# Ararinha4.net
KiCad netlist of a schematic drawn in EAGLE
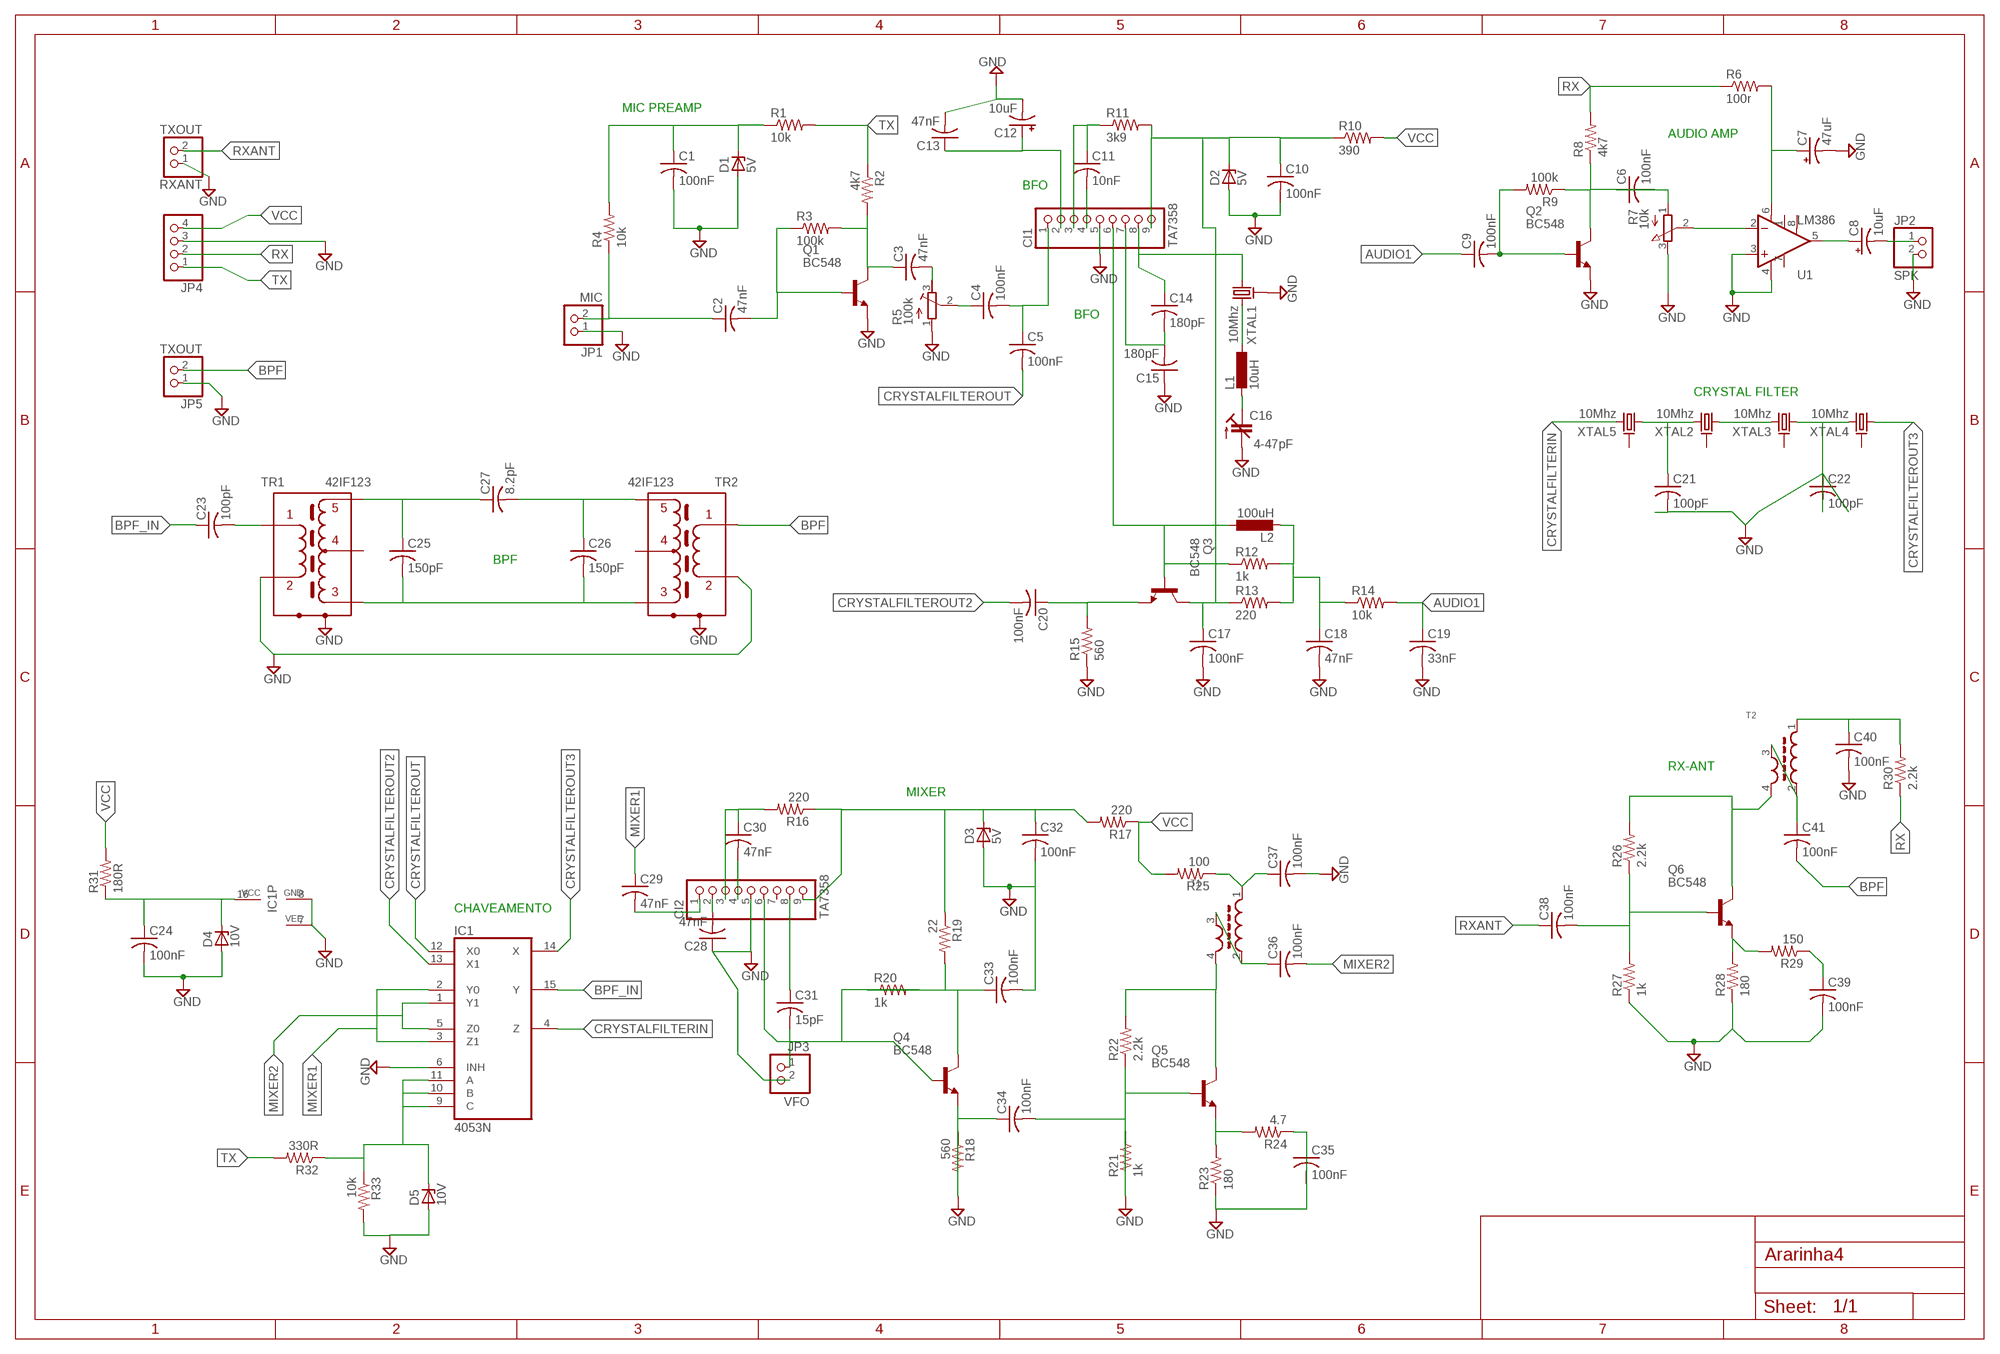
[diagram p0: schematic, sheet 1]

(export (version "E")
  (design (tool "Eeschema 10.0.6"))
  (components
    (comp (ref "C1")
      (value "100nF")
      (footprint "eagle-import:C050-030X075")
      (libsource (lib "eagle-import") (part "C-US050-030X075"))
    )
    (comp (ref "C2")
      (value "47nF")
      (footprint "eagle-import:C050-030X075")
      (libsource (lib "eagle-import") (part "C-US050-030X075"))
    )
    (comp (ref "C3")
      (value "47nF")
      (footprint "eagle-import:C050-030X075")
      (libsource (lib "eagle-import") (part "C-US050-030X075"))
    )
    (comp (ref "C4")
      (value "100nF")
      (footprint "eagle-import:C050-030X075")
      (libsource (lib "eagle-import") (part "C-US050-030X075"))
    )
    (comp (ref "C5")
      (value "100nF")
      (footprint "eagle-import:C050-030X075")
      (libsource (lib "eagle-import") (part "C-US050-030X075"))
    )
    (comp (ref "C6")
      (value "100nF")
      (footprint "eagle-import:C050-030X075")
      (libsource (lib "eagle-import") (part "C-US050-030X075"))
    )
    (comp (ref "C7")
      (value "47uF")
      (footprint "eagle-import:E5-6")
      (libsource (lib "eagle-import") (part "CPOL-USE5-6"))
    )
    (comp (ref "C8")
      (value "10uF")
      (footprint "eagle-import:E5-6")
      (libsource (lib "eagle-import") (part "CPOL-USE5-6"))
    )
    (comp (ref "C9")
      (value "100nF")
      (footprint "eagle-import:C050-030X075")
      (libsource (lib "eagle-import") (part "C-US050-030X075"))
    )
    (comp (ref "C10")
      (value "100nF")
      (footprint "eagle-import:C050-030X075")
      (libsource (lib "eagle-import") (part "C-US050-030X075"))
    )
    (comp (ref "C11")
      (value "10nF")
      (footprint "eagle-import:C050-030X075")
      (libsource (lib "eagle-import") (part "C-US050-030X075"))
    )
    (comp (ref "C12")
      (value "10uF")
      (footprint "eagle-import:E5-6")
      (libsource (lib "eagle-import") (part "CPOL-USE5-6"))
    )
    (comp (ref "C13")
      (value "47nF")
      (footprint "eagle-import:C050-030X075")
      (libsource (lib "eagle-import") (part "C-US050-030X075"))
    )
    (comp (ref "C14")
      (value "180pF")
      (footprint "eagle-import:C050-030X075")
      (libsource (lib "eagle-import") (part "C-US050-030X075"))
    )
    (comp (ref "C15")
      (value "180pF")
      (footprint "eagle-import:C050-030X075")
      (libsource (lib "eagle-import") (part "C-US050-030X075"))
    )
    (comp (ref "C16")
      (value "4-47pF")
      (footprint "eagle-import:CTRIM3050.504")
      (libsource (lib "eagle-import") (part "C-TRIMM3050.504"))
    )
    (comp (ref "C17")
      (value "100nF")
      (footprint "eagle-import:C050-030X075")
      (libsource (lib "eagle-import") (part "C-US050-030X075"))
    )
    (comp (ref "C18")
      (value "47nF")
      (footprint "eagle-import:C050-030X075")
      (libsource (lib "eagle-import") (part "C-US050-030X075"))
    )
    (comp (ref "C19")
      (value "33nF")
      (footprint "eagle-import:C050-030X075")
      (libsource (lib "eagle-import") (part "C-US050-030X075"))
    )
    (comp (ref "C20")
      (value "100nF")
      (footprint "eagle-import:C050-030X075")
      (libsource (lib "eagle-import") (part "C-US050-030X075"))
    )
    (comp (ref "C21")
      (value "100pF")
      (footprint "eagle-import:C050-030X075")
      (libsource (lib "eagle-import") (part "C-US050-030X075"))
    )
    (comp (ref "C22")
      (value "100pF")
      (footprint "eagle-import:C050-030X075")
      (libsource (lib "eagle-import") (part "C-US050-030X075"))
    )
    (comp (ref "C23")
      (value "100pF")
      (footprint "eagle-import:C050-030X075")
      (libsource (lib "eagle-import") (part "C-US050-030X075"))
    )
    (comp (ref "C24")
      (value "100nF")
      (footprint "eagle-import:C050-030X075")
      (libsource (lib "eagle-import") (part "C-US050-030X075"))
    )
    (comp (ref "C25")
      (value "150pF")
      (footprint "eagle-import:C050-030X075")
      (libsource (lib "eagle-import") (part "C-US050-030X075"))
    )
    (comp (ref "C26")
      (value "150pF")
      (footprint "eagle-import:C050-030X075")
      (libsource (lib "eagle-import") (part "C-US050-030X075"))
    )
    (comp (ref "C27")
      (value "8.2pF")
      (footprint "eagle-import:C050-030X075")
      (libsource (lib "eagle-import") (part "C-US050-030X075"))
    )
    (comp (ref "C28")
      (value "47nF")
      (footprint "eagle-import:C050-030X075")
      (libsource (lib "eagle-import") (part "C-US050-030X075"))
    )
    (comp (ref "C29")
      (value "47nF")
      (footprint "eagle-import:C050-030X075")
      (libsource (lib "eagle-import") (part "C-US050-030X075"))
    )
    (comp (ref "C30")
      (value "47nF")
      (footprint "eagle-import:C050-030X075")
      (libsource (lib "eagle-import") (part "C-US050-030X075"))
    )
    (comp (ref "C31")
      (value "15pF")
      (footprint "eagle-import:C050-030X075")
      (libsource (lib "eagle-import") (part "C-US050-030X075"))
    )
    (comp (ref "C32")
      (value "100nF")
      (footprint "eagle-import:C050-030X075")
      (libsource (lib "eagle-import") (part "C-US050-030X075"))
    )
    (comp (ref "C33")
      (value "100nF")
      (footprint "eagle-import:C050-030X075")
      (libsource (lib "eagle-import") (part "C-US050-030X075"))
    )
    (comp (ref "C34")
      (value "100nF")
      (footprint "eagle-import:C050-030X075")
      (libsource (lib "eagle-import") (part "C-US050-030X075"))
    )
    (comp (ref "C35")
      (value "100nF")
      (footprint "eagle-import:C050-030X075")
      (libsource (lib "eagle-import") (part "C-US050-030X075"))
    )
    (comp (ref "C36")
      (value "100nF")
      (footprint "eagle-import:C050-030X075")
      (libsource (lib "eagle-import") (part "C-US050-030X075"))
    )
    (comp (ref "C37")
      (value "100nF")
      (footprint "eagle-import:C050-030X075")
      (libsource (lib "eagle-import") (part "C-US050-030X075"))
    )
    (comp (ref "C38")
      (value "100nF")
      (footprint "eagle-import:C050-030X075")
      (libsource (lib "eagle-import") (part "C-US050-030X075"))
    )
    (comp (ref "C39")
      (value "100nF")
      (footprint "eagle-import:C050-030X075")
      (libsource (lib "eagle-import") (part "C-US050-030X075"))
    )
    (comp (ref "C40")
      (value "100nF")
      (footprint "eagle-import:C050-030X075")
      (libsource (lib "eagle-import") (part "C-US050-030X075"))
    )
    (comp (ref "C41")
      (value "100nF")
      (footprint "eagle-import:C050-030X075")
      (libsource (lib "eagle-import") (part "C-US050-030X075"))
    )
    (comp (ref "CI1")
      (value "TA7358")
      (footprint "eagle-import:1X09")
      (libsource (lib "eagle-import") (part "PINHD-1X9"))
    )
    (comp (ref "CI2")
      (value "TA7358")
      (footprint "eagle-import:1X09")
      (libsource (lib "eagle-import") (part "PINHD-1X9"))
    )
    (comp (ref "D1")
      (value "5V")
      (footprint "eagle-import:ZDIO-5")
      (libsource (lib "eagle-import") (part "ZENER-DIODEZD-5"))
    )
    (comp (ref "D2")
      (value "5V")
      (footprint "eagle-import:ZDIO-5")
      (libsource (lib "eagle-import") (part "ZENER-DIODEZD-5"))
    )
    (comp (ref "D3")
      (value "5V")
      (footprint "eagle-import:ZDIO-5")
      (libsource (lib "eagle-import") (part "ZENER-DIODEZD-5"))
    )
    (comp (ref "D4")
      (value "10V")
      (footprint "eagle-import:ZDIO-5")
      (libsource (lib "eagle-import") (part "ZENER-DIODEZD-5"))
    )
    (comp (ref "D5")
      (value "10V")
      (footprint "eagle-import:ZDIO-5")
      (libsource (lib "eagle-import") (part "ZENER-DIODEZD-5"))
    )
    (comp (ref "IC1")
      (value "4053N")
      (footprint "eagle-import:DIL16")
      (libsource (lib "eagle-import") (part "4053N"))
    )
    (comp (ref "JP1")
      (value "MIC")
      (footprint "eagle-import:1X02")
      (libsource (lib "eagle-import") (part "PINHD-1X2"))
    )
    (comp (ref "JP2")
      (value "SPK")
      (footprint "eagle-import:1X02")
      (libsource (lib "eagle-import") (part "PINHD-1X2"))
    )
    (comp (ref "JP3")
      (value "VFO")
      (footprint "eagle-import:1X02")
      (libsource (lib "eagle-import") (part "PINHD-1X2"))
    )
    (comp (ref "JP4")
      (value "PINHD-1X4")
      (footprint "eagle-import:1X04")
      (libsource (lib "eagle-import") (part "PINHD-1X4"))
    )
    (comp (ref "JP5")
      (value "TXOUT")
      (footprint "eagle-import:1X02")
      (libsource (lib "eagle-import") (part "PINHD-1X2"))
    )
    (comp (ref "L1")
      (value "10uH")
      (footprint "eagle-import:0207_7")
      (libsource (lib "eagle-import") (part "L-EU0207/7"))
    )
    (comp (ref "L2")
      (value "100uH")
      (footprint "eagle-import:0207_7")
      (libsource (lib "eagle-import") (part "L-EU0207/7"))
    )
    (comp (ref "Q1")
      (value "BC548")
      (footprint "eagle-import:TO92-EBC")
      (libsource (lib "eagle-import") (part "BC548"))
    )
    (comp (ref "Q2")
      (value "BC548")
      (footprint "eagle-import:TO92-EBC")
      (libsource (lib "eagle-import") (part "BC548"))
    )
    (comp (ref "Q3")
      (value "BC548")
      (footprint "eagle-import:TO92-EBC")
      (libsource (lib "eagle-import") (part "BC548"))
    )
    (comp (ref "Q4")
      (value "BC548")
      (footprint "eagle-import:TO92-EBC")
      (libsource (lib "eagle-import") (part "BC548"))
    )
    (comp (ref "Q5")
      (value "BC548")
      (footprint "eagle-import:TO92-EBC")
      (libsource (lib "eagle-import") (part "BC548"))
    )
    (comp (ref "Q6")
      (value "BC548")
      (footprint "eagle-import:TO92-EBC")
      (libsource (lib "eagle-import") (part "BC548"))
    )
    (comp (ref "R1")
      (value "10k")
      (footprint "eagle-import:0204_7")
      (libsource (lib "eagle-import") (part "R-US_0204/7"))
    )
    (comp (ref "R2")
      (value "4k7")
      (footprint "eagle-import:0204_7")
      (libsource (lib "eagle-import") (part "R-US_0204/7"))
    )
    (comp (ref "R3")
      (value "100k")
      (footprint "eagle-import:0204_7")
      (libsource (lib "eagle-import") (part "R-US_0204/7"))
    )
    (comp (ref "R4")
      (value "10k")
      (footprint "eagle-import:0204_7")
      (libsource (lib "eagle-import") (part "R-US_0204/7"))
    )
    (comp (ref "R5")
      (value "100k")
      (footprint "eagle-import:RTRIM3299W")
      (libsource (lib "eagle-import") (part "R-TRIMM3299W"))
    )
    (comp (ref "R6")
      (value "100r")
      (footprint "eagle-import:0204_7")
      (libsource (lib "eagle-import") (part "R-US_0204/7"))
    )
    (comp (ref "R7")
      (value "10k")
      (footprint "eagle-import:3RP_1610N")
      (libsource (lib "eagle-import") (part "3RP/1610N"))
    )
    (comp (ref "R8")
      (value "4k7")
      (footprint "eagle-import:0204_7")
      (libsource (lib "eagle-import") (part "R-US_0204/7"))
    )
    (comp (ref "R9")
      (value "100k")
      (footprint "eagle-import:0204_7")
      (libsource (lib "eagle-import") (part "R-US_0204/7"))
    )
    (comp (ref "R10")
      (value "390")
      (footprint "eagle-import:0204_7")
      (libsource (lib "eagle-import") (part "R-US_0204/7"))
    )
    (comp (ref "R11")
      (value "3k9")
      (footprint "eagle-import:0204_7")
      (libsource (lib "eagle-import") (part "R-US_0204/7"))
    )
    (comp (ref "R12")
      (value "1k")
      (footprint "eagle-import:0204_7")
      (libsource (lib "eagle-import") (part "R-US_0204/7"))
    )
    (comp (ref "R13")
      (value "220")
      (footprint "eagle-import:0204_7")
      (libsource (lib "eagle-import") (part "R-US_0204/7"))
    )
    (comp (ref "R14")
      (value "10k")
      (footprint "eagle-import:0204_7")
      (libsource (lib "eagle-import") (part "R-US_0204/7"))
    )
    (comp (ref "R15")
      (value "560")
      (footprint "eagle-import:0204_7")
      (libsource (lib "eagle-import") (part "R-US_0204/7"))
    )
    (comp (ref "R16")
      (value "220")
      (footprint "eagle-import:0204_7")
      (libsource (lib "eagle-import") (part "R-US_0204/7"))
    )
    (comp (ref "R17")
      (value "220")
      (footprint "eagle-import:0204_7")
      (libsource (lib "eagle-import") (part "R-US_0204/7"))
    )
    (comp (ref "R18")
      (value "560")
      (footprint "eagle-import:0204_7")
      (libsource (lib "eagle-import") (part "R-US_0204/7"))
    )
    (comp (ref "R19")
      (value "22")
      (footprint "eagle-import:0204_7")
      (libsource (lib "eagle-import") (part "R-US_0204/7"))
    )
    (comp (ref "R20")
      (value "1k")
      (footprint "eagle-import:0204_7")
      (libsource (lib "eagle-import") (part "R-US_0204/7"))
    )
    (comp (ref "R21")
      (value "1k")
      (footprint "eagle-import:0204_7")
      (libsource (lib "eagle-import") (part "R-US_0204/7"))
    )
    (comp (ref "R22")
      (value "2.2k")
      (footprint "eagle-import:0204_7")
      (libsource (lib "eagle-import") (part "R-US_0204/7"))
    )
    (comp (ref "R23")
      (value "180")
      (footprint "eagle-import:0204_7")
      (libsource (lib "eagle-import") (part "R-US_0204/7"))
    )
    (comp (ref "R24")
      (value "4.7")
      (footprint "eagle-import:0204_7")
      (libsource (lib "eagle-import") (part "R-US_0204/7"))
    )
    (comp (ref "R25")
      (value "100")
      (footprint "eagle-import:0204_7")
      (libsource (lib "eagle-import") (part "R-US_0204/7"))
    )
    (comp (ref "R26")
      (value "2.2k")
      (footprint "eagle-import:0204_7")
      (libsource (lib "eagle-import") (part "R-US_0204/7"))
    )
    (comp (ref "R27")
      (value "1k")
      (footprint "eagle-import:0204_7")
      (libsource (lib "eagle-import") (part "R-US_0204/7"))
    )
    (comp (ref "R28")
      (value "180")
      (footprint "eagle-import:0204_7")
      (libsource (lib "eagle-import") (part "R-US_0204/7"))
    )
    (comp (ref "R29")
      (value "150")
      (footprint "eagle-import:0204_7")
      (libsource (lib "eagle-import") (part "R-US_0204/7"))
    )
    (comp (ref "R30")
      (value "2.2k")
      (footprint "eagle-import:0204_7")
      (libsource (lib "eagle-import") (part "R-US_0204/7"))
    )
    (comp (ref "R31")
      (value "180R")
      (footprint "eagle-import:0204_7")
      (libsource (lib "eagle-import") (part "R-US_0204/7"))
    )
    (comp (ref "R32")
      (value "330R")
      (footprint "eagle-import:0204_7")
      (libsource (lib "eagle-import") (part "R-US_0204/7"))
    )
    (comp (ref "R33")
      (value "10k")
      (footprint "eagle-import:0204_7")
      (libsource (lib "eagle-import") (part "R-US_0204/7"))
    )
    (comp (ref "RXANT")
      (value "TXOUT")
      (footprint "eagle-import:1X02")
      (libsource (lib "eagle-import") (part "PINHD-1X2"))
    )
    (comp (ref "T1")
      (value "TOROID-T37-4PIN")
      (footprint "eagle-import:TOROID-T37-4PIN")
      (libsource (lib "eagle-import") (part "TOROID-T37-4PIN"))
    )
    (comp (ref "T2")
      (value "TOROID-T37-4PIN")
      (footprint "eagle-import:TOROID-T37-4PIN")
      (libsource (lib "eagle-import") (part "TOROID-T37-4PIN"))
    )
    (comp (ref "TR1")
      (value "42IF123")
      (footprint "eagle-import:42IF123")
      (libsource (lib "eagle-import") (part "42IF123"))
    )
    (comp (ref "TR2")
      (value "42IF123")
      (footprint "eagle-import:42IF123")
      (libsource (lib "eagle-import") (part "42IF123"))
    )
    (comp (ref "U1")
      (value "LM386")
      (footprint "eagle-import:DIP08")
      (libsource (lib "eagle-import") (part "LM386"))
    )
    (comp (ref "XTAL1")
      (value "10Mhz")
      (footprint "eagle-import:CRISTAL_EM_PÉ")
      (libsource (lib "eagle-import") (part "CRISTAL_EM_PÉ"))
    )
    (comp (ref "XTAL2")
      (value "10Mhz")
      (footprint "eagle-import:CRISTAL_EM_PÉ")
      (libsource (lib "eagle-import") (part "CRISTAL_EM_PÉ"))
    )
    (comp (ref "XTAL3")
      (value "10Mhz")
      (footprint "eagle-import:CRISTAL_EM_PÉ")
      (libsource (lib "eagle-import") (part "CRISTAL_EM_PÉ"))
    )
    (comp (ref "XTAL4")
      (value "10Mhz")
      (footprint "eagle-import:CRISTAL_EM_PÉ")
      (libsource (lib "eagle-import") (part "CRISTAL_EM_PÉ"))
    )
    (comp (ref "XTAL5")
      (value "10Mhz")
      (footprint "eagle-import:CRISTAL_EM_PÉ")
      (libsource (lib "eagle-import") (part "CRISTAL_EM_PÉ"))
    )
  )
  (nets
    (net (code "1") (name "AUDIO1") (class "Default")
      (node (ref "C19") (pin "1") (pinfunction "1_1") (pintype "passive"))
      (node (ref "C9") (pin "1") (pinfunction "1_1") (pintype "passive"))
      (node (ref "R14") (pin "2") (pinfunction "2_2") (pintype "passive"))
    )
    (net (code "2") (name "BPF") (class "Default")
      (node (ref "C41") (pin "2") (pinfunction "2_2") (pintype "passive"))
      (node (ref "JP5") (pin "2") (pinfunction "2_2") (pintype "passive"))
      (node (ref "TR2") (pin "P$1") (pinfunction "1_P$1") (pintype "bidirectional"))
    )
    (net (code "3") (name "BPF_IN") (class "Default")
      (node (ref "C23") (pin "1") (pinfunction "1_1") (pintype "passive"))
      (node (ref "IC1") (pin "15") (pinfunction "Y_15") (pintype "bidirectional"))
    )
    (net (code "4") (name "CRYSTALFILTERIN") (class "Default")
      (node (ref "IC1") (pin "4") (pinfunction "Z_4") (pintype "bidirectional"))
      (node (ref "XTAL5") (pin "1") (pinfunction "2_1") (pintype "passive"))
    )
    (net (code "5") (name "CRYSTALFILTEROUT") (class "Default")
      (node (ref "C5") (pin "2") (pinfunction "2_2") (pintype "passive"))
      (node (ref "IC1") (pin "12") (pinfunction "X0_12") (pintype "bidirectional"))
    )
    (net (code "6") (name "CRYSTALFILTEROUT2") (class "Default")
      (node (ref "C20") (pin "2") (pinfunction "2_2") (pintype "passive"))
      (node (ref "IC1") (pin "13") (pinfunction "X1_13") (pintype "bidirectional"))
    )
    (net (code "7") (name "CRYSTALFILTEROUT3") (class "Default")
      (node (ref "IC1") (pin "14") (pinfunction "X_14") (pintype "bidirectional"))
      (node (ref "XTAL4") (pin "2") (pinfunction "1_2") (pintype "passive"))
    )
    (net (code "8") (name "GND") (class "Default")
      (node (ref "C1") (pin "2") (pinfunction "2_2") (pintype "passive"))
      (node (ref "C10") (pin "2") (pinfunction "2_2") (pintype "passive"))
      (node (ref "C12") (pin "-") (pinfunction "-_-") (pintype "passive"))
      (node (ref "C13") (pin "2") (pinfunction "2_2") (pintype "passive"))
      (node (ref "C15") (pin "1") (pinfunction "1_1") (pintype "passive"))
      (node (ref "C16") (pin "2") (pinfunction "A_2") (pintype "passive"))
      (node (ref "C17") (pin "2") (pinfunction "2_2") (pintype "passive"))
      (node (ref "C18") (pin "2") (pinfunction "2_2") (pintype "passive"))
      (node (ref "C19") (pin "2") (pinfunction "2_2") (pintype "passive"))
      (node (ref "C21") (pin "2") (pinfunction "2_2") (pintype "passive"))
      (node (ref "C22") (pin "1") (pinfunction "1_1") (pintype "passive"))
      (node (ref "C24") (pin "2") (pinfunction "2_2") (pintype "passive"))
      (node (ref "C28") (pin "1") (pinfunction "1_1") (pintype "passive"))
      (node (ref "C32") (pin "2") (pinfunction "2_2") (pintype "passive"))
      (node (ref "C33") (pin "2") (pinfunction "2_2") (pintype "passive"))
      (node (ref "C35") (pin "1") (pinfunction "1_1") (pintype "passive"))
      (node (ref "C37") (pin "2") (pinfunction "2_2") (pintype "passive"))
      (node (ref "C39") (pin "2") (pinfunction "2_2") (pintype "passive"))
      (node (ref "C40") (pin "2") (pinfunction "2_2") (pintype "passive"))
      (node (ref "C7") (pin "-") (pinfunction "-_-") (pintype "passive"))
      (node (ref "CI1") (pin "5") (pinfunction "5_5") (pintype "passive"))
      (node (ref "CI2") (pin "5") (pinfunction "5_5") (pintype "passive"))
      (node (ref "D1") (pin "A") (pinfunction "A_A") (pintype "passive"))
      (node (ref "D2") (pin "A") (pinfunction "A_A") (pintype "passive"))
      (node (ref "D3") (pin "A") (pinfunction "A_A") (pintype "passive"))
      (node (ref "D4") (pin "A") (pinfunction "A_A") (pintype "passive"))
      (node (ref "D5") (pin "A") (pinfunction "A_A") (pintype "passive"))
      (node (ref "IC1") (pin "6") (pinfunction "INH_6") (pintype "input"))
      (node (ref "IC1") (pin "7") (pinfunction "VEE_7") (pintype "power_in"))
      (node (ref "IC1") (pin "8") (pinfunction "GND_8") (pintype "power_in"))
      (node (ref "JP1") (pin "1") (pinfunction "1_1") (pintype "passive"))
      (node (ref "JP2") (pin "2") (pinfunction "2_2") (pintype "passive"))
      (node (ref "JP3") (pin "2") (pinfunction "2_2") (pintype "passive"))
      (node (ref "JP4") (pin "3") (pinfunction "3_3") (pintype "passive"))
      (node (ref "JP5") (pin "1") (pinfunction "1_1") (pintype "passive"))
      (node (ref "Q1") (pin "E") (pinfunction "E_E") (pintype "passive"))
      (node (ref "Q2") (pin "E") (pinfunction "E_E") (pintype "passive"))
      (node (ref "R15") (pin "1") (pinfunction "1_1") (pintype "passive"))
      (node (ref "R18") (pin "1") (pinfunction "1_1") (pintype "passive"))
      (node (ref "R21") (pin "2") (pinfunction "2_2") (pintype "passive"))
      (node (ref "R23") (pin "1") (pinfunction "1_1") (pintype "passive"))
      (node (ref "R27") (pin "1") (pinfunction "1_1") (pintype "passive"))
      (node (ref "R28") (pin "1") (pinfunction "1_1") (pintype "passive"))
      (node (ref "R33") (pin "2") (pinfunction "2_2") (pintype "passive"))
      (node (ref "R5") (pin "1") (pinfunction "E_1") (pintype "passive"))
      (node (ref "R7") (pin "3") (pinfunction "E_3") (pintype "passive"))
      (node (ref "RXANT") (pin "1") (pinfunction "1_1") (pintype "passive"))
      (node (ref "TR1") (pin "P$2") (pinfunction "2_P$2") (pintype "bidirectional"))
      (node (ref "TR1") (pin "P$7") (pinfunction "7_P$7") (pintype "bidirectional"))
      (node (ref "TR2") (pin "P$2") (pinfunction "2_P$2") (pintype "bidirectional"))
      (node (ref "TR2") (pin "P$6") (pinfunction "6_P$6") (pintype "bidirectional"))
      (node (ref "U1") (pin "3") (pinfunction "+IN_3") (pintype "input"))
      (node (ref "U1") (pin "4") (pinfunction "V-_4") (pintype "power_in"))
      (node (ref "XTAL1") (pin "GND") (pinfunction "GND_GND") (pintype "passive"))
    )
    (net (code "9") (name "MIXER1") (class "Default")
      (node (ref "C29") (pin "1") (pinfunction "1_1") (pintype "passive"))
      (node (ref "IC1") (pin "2") (pinfunction "Y0_2") (pintype "bidirectional"))
      (node (ref "IC1") (pin "3") (pinfunction "Z1_3") (pintype "bidirectional"))
    )
    (net (code "10") (name "MIXER2") (class "Default")
      (node (ref "C36") (pin "2") (pinfunction "2_2") (pintype "passive"))
      (node (ref "IC1") (pin "1") (pinfunction "Y1_1") (pintype "bidirectional"))
      (node (ref "IC1") (pin "5") (pinfunction "Z0_5") (pintype "bidirectional"))
    )
    (net (code "11") (name "Net-(C1-Pad1)") (class "Default")
      (node (ref "C1") (pin "1") (pinfunction "1_1") (pintype "passive"))
      (node (ref "D1") (pin "C") (pinfunction "C_C") (pintype "passive"))
      (node (ref "R1") (pin "1") (pinfunction "1_1") (pintype "passive"))
      (node (ref "R4") (pin "2") (pinfunction "2_2") (pintype "passive"))
    )
    (net (code "12") (name "Net-(C2-Pad1)") (class "Default")
      (node (ref "C2") (pin "1") (pinfunction "1_1") (pintype "passive"))
      (node (ref "JP1") (pin "2") (pinfunction "2_2") (pintype "passive"))
      (node (ref "R4") (pin "1") (pinfunction "1_1") (pintype "passive"))
    )
    (net (code "13") (name "Net-(C2-Pad2)") (class "Default")
      (node (ref "C2") (pin "2") (pinfunction "2_2") (pintype "passive"))
      (node (ref "Q1") (pin "B") (pinfunction "B_B") (pintype "passive"))
      (node (ref "R3") (pin "1") (pinfunction "1_1") (pintype "passive"))
    )
    (net (code "14") (name "Net-(C3-Pad1)") (class "Default")
      (node (ref "C3") (pin "1") (pinfunction "1_1") (pintype "passive"))
      (node (ref "Q1") (pin "C") (pinfunction "C_C") (pintype "passive"))
      (node (ref "R2") (pin "2") (pinfunction "2_2") (pintype "passive"))
      (node (ref "R3") (pin "2") (pinfunction "2_2") (pintype "passive"))
    )
    (net (code "15") (name "Net-(C4-Pad2)") (class "Default")
      (node (ref "C4") (pin "2") (pinfunction "2_2") (pintype "passive"))
      (node (ref "C5") (pin "1") (pinfunction "1_1") (pintype "passive"))
      (node (ref "CI1") (pin "1") (pinfunction "1_1") (pintype "passive"))
    )
    (net (code "16") (name "Net-(C6-Pad2)") (class "Default")
      (node (ref "C6") (pin "2") (pinfunction "2_2") (pintype "passive"))
      (node (ref "Q2") (pin "C") (pinfunction "C_C") (pintype "passive"))
      (node (ref "R8") (pin "1") (pinfunction "1_1") (pintype "passive"))
      (node (ref "R9") (pin "1") (pinfunction "1_1") (pintype "passive"))
    )
    (net (code "17") (name "Net-(C8-Pad-)") (class "Default")
      (node (ref "C8") (pin "-") (pinfunction "-_-") (pintype "passive"))
      (node (ref "JP2") (pin "1") (pinfunction "1_1") (pintype "passive"))
    )
    (net (code "18") (name "Net-(C9-Pad2)") (class "Default")
      (node (ref "C9") (pin "2") (pinfunction "2_2") (pintype "passive"))
      (node (ref "Q2") (pin "B") (pinfunction "B_B") (pintype "passive"))
      (node (ref "R9") (pin "2") (pinfunction "2_2") (pintype "passive"))
    )
    (net (code "19") (name "Net-(C10-Pad1)") (class "Default")
      (node (ref "C10") (pin "1") (pinfunction "1_1") (pintype "passive"))
      (node (ref "C17") (pin "1") (pinfunction "1_1") (pintype "passive"))
      (node (ref "CI1") (pin "9") (pinfunction "9_9") (pintype "passive"))
      (node (ref "D2") (pin "C") (pinfunction "C_C") (pintype "passive"))
      (node (ref "Q3") (pin "C") (pinfunction "C_C") (pintype "passive"))
      (node (ref "R10") (pin "1") (pinfunction "1_1") (pintype "passive"))
      (node (ref "R11") (pin "2") (pinfunction "2_2") (pintype "passive"))
      (node (ref "R13") (pin "1") (pinfunction "1_1") (pintype "passive"))
    )
    (net (code "20") (name "Net-(C11-Pad1)") (class "Default")
      (node (ref "C11") (pin "1") (pinfunction "1_1") (pintype "passive"))
      (node (ref "CI1") (pin "3") (pinfunction "3_3") (pintype "passive"))
      (node (ref "R11") (pin "1") (pinfunction "1_1") (pintype "passive"))
    )
    (net (code "21") (name "Net-(C11-Pad2)") (class "Default")
      (node (ref "C11") (pin "2") (pinfunction "2_2") (pintype "passive"))
      (node (ref "CI1") (pin "4") (pinfunction "4_4") (pintype "passive"))
    )
    (net (code "22") (name "Net-(C12-Pad+)") (class "Default")
      (node (ref "C12") (pin "+") (pinfunction "+_+") (pintype "passive"))
      (node (ref "C13") (pin "1") (pinfunction "1_1") (pintype "passive"))
      (node (ref "CI1") (pin "2") (pinfunction "2_2") (pintype "passive"))
    )
    (net (code "23") (name "Net-(C14-Pad2)") (class "Default")
      (node (ref "C14") (pin "2") (pinfunction "2_2") (pintype "passive"))
      (node (ref "C15") (pin "2") (pinfunction "2_2") (pintype "passive"))
      (node (ref "CI1") (pin "7") (pinfunction "7_7") (pintype "passive"))
    )
    (net (code "24") (name "Net-(C16-E)") (class "Default")
      (node (ref "C16") (pin "1") (pinfunction "E_1") (pintype "passive"))
      (node (ref "L1") (pin "2") (pinfunction "2_2") (pintype "passive"))
    )
    (net (code "25") (name "Net-(C18-Pad1)") (class "Default")
      (node (ref "C18") (pin "1") (pinfunction "1_1") (pintype "passive"))
      (node (ref "L2") (pin "2") (pinfunction "2_2") (pintype "passive"))
      (node (ref "R12") (pin "2") (pinfunction "2_2") (pintype "passive"))
      (node (ref "R13") (pin "2") (pinfunction "2_2") (pintype "passive"))
      (node (ref "R14") (pin "1") (pinfunction "1_1") (pintype "passive"))
    )
    (net (code "26") (name "Net-(C20-Pad1)") (class "Default")
      (node (ref "C20") (pin "1") (pinfunction "1_1") (pintype "passive"))
      (node (ref "Q3") (pin "E") (pinfunction "E_E") (pintype "passive"))
      (node (ref "R15") (pin "2") (pinfunction "2_2") (pintype "passive"))
    )
    (net (code "27") (name "Net-(C28-Pad2)") (class "Default")
      (node (ref "C28") (pin "2") (pinfunction "2_2") (pintype "passive"))
      (node (ref "CI2") (pin "2") (pinfunction "2_2") (pintype "passive"))
    )
    (net (code "28") (name "Net-(C29-Pad2)") (class "Default")
      (node (ref "C29") (pin "2") (pinfunction "2_2") (pintype "passive"))
      (node (ref "CI2") (pin "1") (pinfunction "1_1") (pintype "passive"))
    )
    (net (code "29") (name "Net-(C30-Pad1)") (class "Default")
      (node (ref "C30") (pin "1") (pinfunction "1_1") (pintype "passive"))
      (node (ref "CI2") (pin "3") (pinfunction "3_3") (pintype "passive"))
      (node (ref "R16") (pin "2") (pinfunction "2_2") (pintype "passive"))
    )
    (net (code "30") (name "Net-(C30-Pad2)") (class "Default")
      (node (ref "C30") (pin "2") (pinfunction "2_2") (pintype "passive"))
      (node (ref "CI2") (pin "4") (pinfunction "4_4") (pintype "passive"))
    )
    (net (code "31") (name "Net-(C31-Pad1)") (class "Default")
      (node (ref "C31") (pin "1") (pinfunction "1_1") (pintype "passive"))
      (node (ref "CI2") (pin "8") (pinfunction "8_8") (pintype "passive"))
    )
    (net (code "32") (name "Net-(C31-Pad2)") (class "Default")
      (node (ref "C31") (pin "2") (pinfunction "2_2") (pintype "passive"))
      (node (ref "JP3") (pin "1") (pinfunction "1_1") (pintype "passive"))
    )
    (net (code "33") (name "Net-(C32-Pad1)") (class "Default")
      (node (ref "C32") (pin "1") (pinfunction "1_1") (pintype "passive"))
      (node (ref "CI2") (pin "9") (pinfunction "9_9") (pintype "passive"))
      (node (ref "D3") (pin "C") (pinfunction "C_C") (pintype "passive"))
      (node (ref "R16") (pin "1") (pinfunction "1_1") (pintype "passive"))
      (node (ref "R17") (pin "2") (pinfunction "2_2") (pintype "passive"))
      (node (ref "R19") (pin "1") (pinfunction "1_1") (pintype "passive"))
    )
    (net (code "34") (name "Net-(C33-Pad1)") (class "Default")
      (node (ref "C33") (pin "1") (pinfunction "1_1") (pintype "passive"))
      (node (ref "Q4") (pin "C") (pinfunction "C_C") (pintype "passive"))
      (node (ref "R19") (pin "2") (pinfunction "2_2") (pintype "passive"))
      (node (ref "R20") (pin "1") (pinfunction "1_1") (pintype "passive"))
    )
    (net (code "35") (name "Net-(C34-Pad1)") (class "Default")
      (node (ref "C34") (pin "1") (pinfunction "1_1") (pintype "passive"))
      (node (ref "Q4") (pin "E") (pinfunction "E_E") (pintype "passive"))
      (node (ref "R18") (pin "2") (pinfunction "2_2") (pintype "passive"))
    )
    (net (code "36") (name "Net-(C34-Pad2)") (class "Default")
      (node (ref "C34") (pin "2") (pinfunction "2_2") (pintype "passive"))
      (node (ref "Q5") (pin "B") (pinfunction "B_B") (pintype "passive"))
      (node (ref "R21") (pin "1") (pinfunction "1_1") (pintype "passive"))
      (node (ref "R22") (pin "1") (pinfunction "1_1") (pintype "passive"))
    )
    (net (code "37") (name "Net-(C35-Pad2)") (class "Default")
      (node (ref "C35") (pin "2") (pinfunction "2_2") (pintype "passive"))
      (node (ref "R24") (pin "1") (pinfunction "1_1") (pintype "passive"))
    )
    (net (code "38") (name "Net-(C36-Pad1)") (class "Default")
      (node (ref "C36") (pin "1") (pinfunction "1_1") (pintype "passive"))
      (node (ref "T1") (pin "2") (pinfunction "2_2") (pintype "bidirectional"))
      (node (ref "T1") (pin "3") (pinfunction "3_3") (pintype "bidirectional"))
    )
    (net (code "39") (name "Net-(C37-Pad1)") (class "Default")
      (node (ref "C37") (pin "1") (pinfunction "1_1") (pintype "passive"))
      (node (ref "R25") (pin "1") (pinfunction "1_1") (pintype "passive"))
      (node (ref "T1") (pin "1") (pinfunction "1_1") (pintype "bidirectional"))
    )
    (net (code "40") (name "Net-(C38-Pad2)") (class "Default")
      (node (ref "C38") (pin "2") (pinfunction "2_2") (pintype "passive"))
      (node (ref "Q6") (pin "B") (pinfunction "B_B") (pintype "passive"))
      (node (ref "R26") (pin "1") (pinfunction "1_1") (pintype "passive"))
      (node (ref "R27") (pin "2") (pinfunction "2_2") (pintype "passive"))
    )
    (net (code "41") (name "Net-(C39-Pad1)") (class "Default")
      (node (ref "C39") (pin "1") (pinfunction "1_1") (pintype "passive"))
      (node (ref "R29") (pin "1") (pinfunction "1_1") (pintype "passive"))
    )
    (net (code "42") (name "Net-(C40-Pad1)") (class "Default")
      (node (ref "C40") (pin "1") (pinfunction "1_1") (pintype "passive"))
      (node (ref "R30") (pin "2") (pinfunction "2_2") (pintype "passive"))
      (node (ref "T2") (pin "1") (pinfunction "1_1") (pintype "bidirectional"))
    )
    (net (code "43") (name "Net-(C41-Pad1)") (class "Default")
      (node (ref "C41") (pin "1") (pinfunction "1_1") (pintype "passive"))
      (node (ref "T2") (pin "2") (pinfunction "2_2") (pintype "bidirectional"))
      (node (ref "T2") (pin "3") (pinfunction "3_3") (pintype "bidirectional"))
    )
    (net (code "44") (name "Net-(CI1-Pad6)") (class "Default")
      (node (ref "CI1") (pin "6") (pinfunction "6_6") (pintype "passive"))
      (node (ref "L2") (pin "1") (pinfunction "1_1") (pintype "passive"))
      (node (ref "Q3") (pin "B") (pinfunction "B_B") (pintype "passive"))
      (node (ref "R12") (pin "1") (pinfunction "1_1") (pintype "passive"))
    )
    (net (code "45") (name "Net-(CI2-Pad6)") (class "Default")
      (node (ref "CI2") (pin "6") (pinfunction "6_6") (pintype "passive"))
      (node (ref "Q4") (pin "B") (pinfunction "B_B") (pintype "passive"))
      (node (ref "R20") (pin "2") (pinfunction "2_2") (pintype "passive"))
    )
    (net (code "46") (name "Net-(IC1A-A)") (class "Default")
      (node (ref "D5") (pin "C") (pinfunction "C_C") (pintype "passive"))
      (node (ref "IC1") (pin "10") (pinfunction "B_10") (pintype "input"))
      (node (ref "IC1") (pin "11") (pinfunction "A_11") (pintype "input"))
      (node (ref "IC1") (pin "9") (pinfunction "C_9") (pintype "input"))
      (node (ref "R32") (pin "1") (pinfunction "1_1") (pintype "passive"))
      (node (ref "R33") (pin "1") (pinfunction "1_1") (pintype "passive"))
    )
    (net (code "47") (name "Net-(IC1B-VCC)") (class "Default")
      (node (ref "C24") (pin "1") (pinfunction "1_1") (pintype "passive"))
      (node (ref "D4") (pin "C") (pinfunction "C_C") (pintype "passive"))
      (node (ref "IC1") (pin "16") (pinfunction "VCC_16") (pintype "power_in"))
      (node (ref "R31") (pin "1") (pinfunction "1_1") (pintype "passive"))
    )
    (net (code "48") (name "Net-(Q5-PadC)") (class "Default")
      (node (ref "Q5") (pin "C") (pinfunction "C_C") (pintype "passive"))
      (node (ref "R22") (pin "2") (pinfunction "2_2") (pintype "passive"))
      (node (ref "T1") (pin "4") (pinfunction "4_4") (pintype "bidirectional"))
    )
    (net (code "49") (name "Net-(Q5-PadE)") (class "Default")
      (node (ref "Q5") (pin "E") (pinfunction "E_E") (pintype "passive"))
      (node (ref "R23") (pin "2") (pinfunction "2_2") (pintype "passive"))
      (node (ref "R24") (pin "2") (pinfunction "2_2") (pintype "passive"))
    )
    (net (code "50") (name "Net-(Q6-PadC)") (class "Default")
      (node (ref "Q6") (pin "C") (pinfunction "C_C") (pintype "passive"))
      (node (ref "R26") (pin "2") (pinfunction "2_2") (pintype "passive"))
      (node (ref "T2") (pin "4") (pinfunction "4_4") (pintype "bidirectional"))
    )
    (net (code "51") (name "Net-(Q6-PadE)") (class "Default")
      (node (ref "Q6") (pin "E") (pinfunction "E_E") (pintype "passive"))
      (node (ref "R28") (pin "2") (pinfunction "2_2") (pintype "passive"))
      (node (ref "R29") (pin "2") (pinfunction "2_2") (pintype "passive"))
    )
    (net (code "52") (name "Net-(R5-A)") (class "Default")
      (node (ref "C3") (pin "2") (pinfunction "2_2") (pintype "passive"))
      (node (ref "R5") (pin "3") (pinfunction "A_3") (pintype "passive"))
    )
    (net (code "53") (name "Net-(R5-S)") (class "Default")
      (node (ref "C4") (pin "1") (pinfunction "1_1") (pintype "passive"))
      (node (ref "R5") (pin "2") (pinfunction "S_2") (pintype "passive"))
    )
    (net (code "54") (name "Net-(R7-A)") (class "Default")
      (node (ref "C6") (pin "1") (pinfunction "1_1") (pintype "passive"))
      (node (ref "R7") (pin "1") (pinfunction "A_1") (pintype "passive"))
    )
    (net (code "55") (name "Net-(R7-S)") (class "Default")
      (node (ref "R7") (pin "2") (pinfunction "S_2") (pintype "passive"))
      (node (ref "U1") (pin "2") (pinfunction "-IN_2") (pintype "input"))
    )
    (net (code "56") (name "Net-(TR1-1)") (class "Default")
      (node (ref "C23") (pin "2") (pinfunction "2_2") (pintype "passive"))
      (node (ref "TR1") (pin "P$1") (pinfunction "1_P$1") (pintype "bidirectional"))
    )
    (net (code "57") (name "Net-(TR1-3)") (class "Default")
      (node (ref "C25") (pin "2") (pinfunction "2_2") (pintype "passive"))
      (node (ref "C26") (pin "2") (pinfunction "2_2") (pintype "passive"))
      (node (ref "TR1") (pin "P$3") (pinfunction "3_P$3") (pintype "bidirectional"))
      (node (ref "TR2") (pin "P$3") (pinfunction "3_P$3") (pintype "bidirectional"))
    )
    (net (code "58") (name "Net-(TR1-5)") (class "Default")
      (node (ref "C25") (pin "1") (pinfunction "1_1") (pintype "passive"))
      (node (ref "C27") (pin "1") (pinfunction "1_1") (pintype "passive"))
      (node (ref "TR1") (pin "P$5") (pinfunction "5_P$5") (pintype "bidirectional"))
    )
    (net (code "59") (name "Net-(TR2-5)") (class "Default")
      (node (ref "C26") (pin "1") (pinfunction "1_1") (pintype "passive"))
      (node (ref "C27") (pin "2") (pinfunction "2_2") (pintype "passive"))
      (node (ref "TR2") (pin "P$5") (pinfunction "5_P$5") (pintype "bidirectional"))
    )
    (net (code "60") (name "Net-(U1-OUT)") (class "Default")
      (node (ref "C8") (pin "+") (pinfunction "+_+") (pintype "passive"))
      (node (ref "U1") (pin "5") (pinfunction "OUT_5") (pintype "output"))
    )
    (net (code "61") (name "Net-(U1-V+)") (class "Default")
      (node (ref "C7") (pin "+") (pinfunction "+_+") (pintype "passive"))
      (node (ref "R6") (pin "2") (pinfunction "2_2") (pintype "passive"))
      (node (ref "U1") (pin "6") (pinfunction "V+_6") (pintype "power_in"))
    )
    (net (code "62") (name "Net-(XTAL1-1)") (class "Default")
      (node (ref "C14") (pin "1") (pinfunction "1_1") (pintype "passive"))
      (node (ref "CI1") (pin "8") (pinfunction "8_8") (pintype "passive"))
      (node (ref "XTAL1") (pin "2") (pinfunction "1_2") (pintype "passive"))
    )
    (net (code "63") (name "Net-(XTAL1-2)") (class "Default")
      (node (ref "L1") (pin "1") (pinfunction "1_1") (pintype "passive"))
      (node (ref "XTAL1") (pin "1") (pinfunction "2_1") (pintype "passive"))
    )
    (net (code "64") (name "Net-(XTAL2-1)") (class "Default")
      (node (ref "XTAL2") (pin "2") (pinfunction "1_2") (pintype "passive"))
      (node (ref "XTAL3") (pin "1") (pinfunction "2_1") (pintype "passive"))
    )
    (net (code "65") (name "Net-(XTAL2-2)") (class "Default")
      (node (ref "C21") (pin "1") (pinfunction "1_1") (pintype "passive"))
      (node (ref "XTAL2") (pin "1") (pinfunction "2_1") (pintype "passive"))
      (node (ref "XTAL5") (pin "2") (pinfunction "1_2") (pintype "passive"))
    )
    (net (code "66") (name "Net-(XTAL3-1)") (class "Default")
      (node (ref "C22") (pin "2") (pinfunction "2_2") (pintype "passive"))
      (node (ref "XTAL3") (pin "2") (pinfunction "1_2") (pintype "passive"))
      (node (ref "XTAL4") (pin "1") (pinfunction "2_1") (pintype "passive"))
    )
    (net (code "67") (name "RX") (class "Default")
      (node (ref "JP4") (pin "2") (pinfunction "2_2") (pintype "passive"))
      (node (ref "R30") (pin "1") (pinfunction "1_1") (pintype "passive"))
      (node (ref "R6") (pin "1") (pinfunction "1_1") (pintype "passive"))
      (node (ref "R8") (pin "2") (pinfunction "2_2") (pintype "passive"))
    )
    (net (code "68") (name "RXANT") (class "Default")
      (node (ref "C38") (pin "1") (pinfunction "1_1") (pintype "passive"))
      (node (ref "RXANT") (pin "2") (pinfunction "2_2") (pintype "passive"))
    )
    (net (code "69") (name "TX") (class "Default")
      (node (ref "JP4") (pin "1") (pinfunction "1_1") (pintype "passive"))
      (node (ref "R1") (pin "2") (pinfunction "2_2") (pintype "passive"))
      (node (ref "R2") (pin "1") (pinfunction "1_1") (pintype "passive"))
      (node (ref "R32") (pin "2") (pinfunction "2_2") (pintype "passive"))
    )
    (net (code "70") (name "VCC") (class "Default")
      (node (ref "JP4") (pin "4") (pinfunction "4_4") (pintype "passive"))
      (node (ref "R10") (pin "2") (pinfunction "2_2") (pintype "passive"))
      (node (ref "R17") (pin "1") (pinfunction "1_1") (pintype "passive"))
      (node (ref "R25") (pin "2") (pinfunction "2_2") (pintype "passive"))
      (node (ref "R31") (pin "2") (pinfunction "2_2") (pintype "passive"))
    )
    (net (code "71") (name "unconnected-(CI2-Pad7)") (class "Default")
      (node (ref "CI2") (pin "7") (pinfunction "7_7") (pintype "passive"))
    )
    (net (code "72") (name "unconnected-(TR1-4-PadP$4)") (class "Default")
      (node (ref "TR1") (pin "P$4") (pinfunction "4_P$4") (pintype "bidirectional"))
    )
    (net (code "73") (name "unconnected-(TR1-6-PadP$6)") (class "Default")
      (node (ref "TR1") (pin "P$6") (pinfunction "6_P$6") (pintype "bidirectional"))
    )
    (net (code "74") (name "unconnected-(TR2-4-PadP$4)") (class "Default")
      (node (ref "TR2") (pin "P$4") (pinfunction "4_P$4") (pintype "bidirectional"))
    )
    (net (code "75") (name "unconnected-(TR2-7-PadP$7)") (class "Default")
      (node (ref "TR2") (pin "P$7") (pinfunction "7_P$7") (pintype "bidirectional"))
    )
    (net (code "76") (name "unconnected-(U1-BP-Pad7)") (class "Default")
      (node (ref "U1") (pin "7") (pinfunction "BP_7") (pintype "bidirectional"))
    )
    (net (code "77") (name "unconnected-(U1-GAIN-Pad1)") (class "Default")
      (node (ref "U1") (pin "1") (pinfunction "GAIN_1") (pintype "bidirectional"))
    )
    (net (code "78") (name "unconnected-(U1-GAIN-Pad8)") (class "Default")
      (node (ref "U1") (pin "8") (pinfunction "GAIN_8") (pintype "bidirectional"))
    )
    (net (code "79") (name "unconnected-(XTAL2-PadGND)") (class "Default")
      (node (ref "XTAL2") (pin "GND") (pinfunction "GND_GND") (pintype "passive"))
    )
    (net (code "80") (name "unconnected-(XTAL3-PadGND)") (class "Default")
      (node (ref "XTAL3") (pin "GND") (pinfunction "GND_GND") (pintype "passive"))
    )
    (net (code "81") (name "unconnected-(XTAL4-PadGND)") (class "Default")
      (node (ref "XTAL4") (pin "GND") (pinfunction "GND_GND") (pintype "passive"))
    )
    (net (code "82") (name "unconnected-(XTAL5-PadGND)") (class "Default")
      (node (ref "XTAL5") (pin "GND") (pinfunction "GND_GND") (pintype "passive"))
    )
  )
)
